# nanoPhant.net
KiCad netlist of a schematic drawn in EAGLE
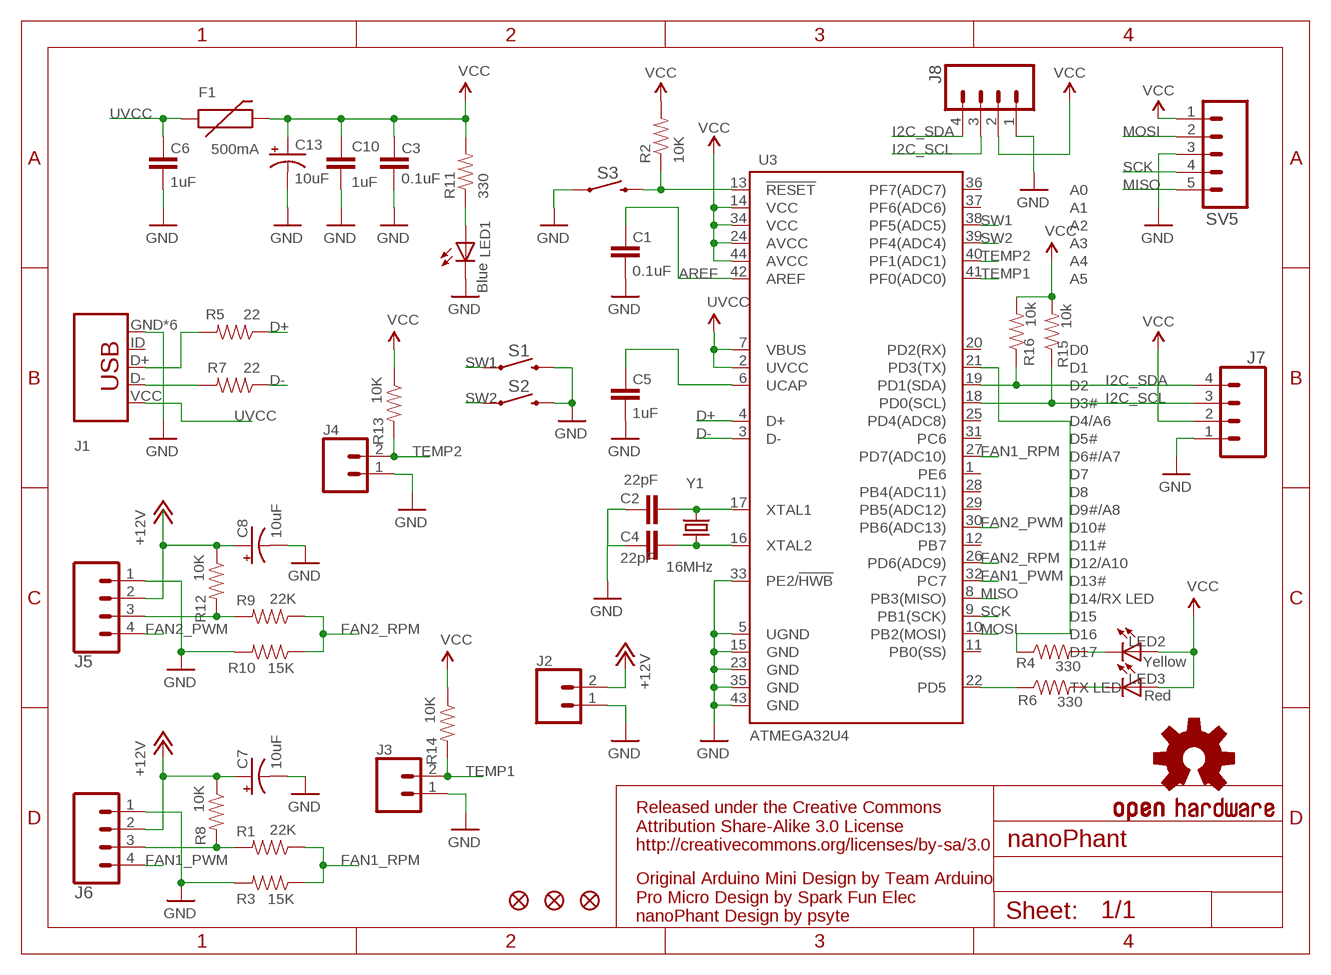
[diagram p0: schematic, sheet 1]

(export (version "E")
  (design (tool "Eeschema 10.0.6"))
  (components
    (comp (ref "C1")
      (value "0.1uF")
      (footprint "eagle-import:C0603")
      (libsource (lib "eagle-import") (part "C-EUC0603"))
    )
    (comp (ref "C2")
      (value "22pF")
      (footprint "eagle-import:C0603")
      (libsource (lib "eagle-import") (part "C-EUC0603"))
    )
    (comp (ref "C3")
      (value "0.1uF")
      (footprint "eagle-import:C0603")
      (libsource (lib "eagle-import") (part "C-EUC0603"))
    )
    (comp (ref "C4")
      (value "22pF")
      (footprint "eagle-import:C0603")
      (libsource (lib "eagle-import") (part "C-EUC0603"))
    )
    (comp (ref "C5")
      (value "1uF")
      (footprint "eagle-import:C0603")
      (libsource (lib "eagle-import") (part "C-EUC0603"))
    )
    (comp (ref "C6")
      (value "1uF")
      (footprint "eagle-import:C0603")
      (libsource (lib "eagle-import") (part "C-EUC0603"))
    )
    (comp (ref "C7")
      (value "10uF")
      (footprint "eagle-import:EIA3216")
      (libsource (lib "eagle-import") (part "CAP_POL1206"))
    )
    (comp (ref "C8")
      (value "10uF")
      (footprint "eagle-import:EIA3216")
      (libsource (lib "eagle-import") (part "CAP_POL1206"))
    )
    (comp (ref "C10")
      (value "1uF")
      (footprint "eagle-import:C0603")
      (libsource (lib "eagle-import") (part "C-EUC0603"))
    )
    (comp (ref "C13")
      (value "10uF")
      (footprint "eagle-import:EIA3216")
      (libsource (lib "eagle-import") (part "CAP_POL1206"))
    )
    (comp (ref "F1")
      (value "500mA")
      (footprint "eagle-import:PTC-1206")
      (libsource (lib "eagle-import") (part "PTCSMD"))
    )
    (comp (ref "FD1")
      (value "FIDUCIAL1X2")
      (footprint "eagle-import:FIDUCIAL-1X2")
      (libsource (lib "eagle-import") (part "FIDUCIAL1X2"))
    )
    (comp (ref "FD2")
      (value "FIDUCIAL1X2")
      (footprint "eagle-import:FIDUCIAL-1X2")
      (libsource (lib "eagle-import") (part "FIDUCIAL1X2"))
    )
    (comp (ref "FD3")
      (value "FIDUCIAL1X2")
      (footprint "eagle-import:FIDUCIAL-1X2")
      (libsource (lib "eagle-import") (part "FIDUCIAL1X2"))
    )
    (comp (ref "J1")
      (value "AMP FCI 10103594-0001LF")
      (footprint "eagle-import:MICRO_USB_4_LEGS")
      (libsource (lib "eagle-import") (part "MICRO-USB-B"))
    )
    (comp (ref "J2")
      (value "CONN_02")
      (footprint "eagle-import:1X02")
      (libsource (lib "eagle-import") (part "CONN_02"))
    )
    (comp (ref "J3")
      (value "CONN_02")
      (footprint "eagle-import:1X02")
      (libsource (lib "eagle-import") (part "CONN_02"))
    )
    (comp (ref "J4")
      (value "CONN_02")
      (footprint "eagle-import:1X02")
      (libsource (lib "eagle-import") (part "CONN_02"))
    )
    (comp (ref "J5")
      (value "CONN_04")
      (footprint "eagle-import:1X04")
      (libsource (lib "eagle-import") (part "CONN_04"))
    )
    (comp (ref "J6")
      (value "CONN_04")
      (footprint "eagle-import:1X04")
      (libsource (lib "eagle-import") (part "CONN_04"))
    )
    (comp (ref "J7")
      (value "CONN_04")
      (footprint "eagle-import:1X04")
      (libsource (lib "eagle-import") (part "CONN_04"))
    )
    (comp (ref "J8")
      (value "CONN_04")
      (footprint "eagle-import:1X04")
      (libsource (lib "eagle-import") (part "CONN_04"))
    )
    (comp (ref "LED1")
      (value "Blue")
      (footprint "eagle-import:LED-0603")
      (libsource (lib "eagle-import") (part "LED0603"))
    )
    (comp (ref "LED2")
      (value "Yellow")
      (footprint "eagle-import:LED-0603")
      (libsource (lib "eagle-import") (part "LED0603"))
    )
    (comp (ref "LED3")
      (value "Red")
      (footprint "eagle-import:LED-0603")
      (libsource (lib "eagle-import") (part "LED0603"))
    )
    (comp (ref "R1")
      (value "22K")
      (footprint "eagle-import:0603-RES")
      (libsource (lib "eagle-import") (part "RESISTOR0603-RES"))
    )
    (comp (ref "R2")
      (value "10K")
      (footprint "eagle-import:0603-RES")
      (libsource (lib "eagle-import") (part "RESISTOR0603-RES"))
    )
    (comp (ref "R3")
      (value "15K")
      (footprint "eagle-import:0603-RES")
      (libsource (lib "eagle-import") (part "RESISTOR0603-RES"))
    )
    (comp (ref "R4")
      (value "330")
      (footprint "eagle-import:0603-RES")
      (libsource (lib "eagle-import") (part "RESISTOR0603-RES"))
    )
    (comp (ref "R5")
      (value "22")
      (footprint "eagle-import:0603-RES")
      (libsource (lib "eagle-import") (part "RESISTOR0603-RES"))
    )
    (comp (ref "R6")
      (value "330")
      (footprint "eagle-import:0603-RES")
      (libsource (lib "eagle-import") (part "RESISTOR0603-RES"))
    )
    (comp (ref "R7")
      (value "22")
      (footprint "eagle-import:0603-RES")
      (libsource (lib "eagle-import") (part "RESISTOR0603-RES"))
    )
    (comp (ref "R8")
      (value "10K")
      (footprint "eagle-import:0603-RES")
      (libsource (lib "eagle-import") (part "RESISTOR0603-RES"))
    )
    (comp (ref "R9")
      (value "22K")
      (footprint "eagle-import:0603-RES")
      (libsource (lib "eagle-import") (part "RESISTOR0603-RES"))
    )
    (comp (ref "R10")
      (value "15K")
      (footprint "eagle-import:0603-RES")
      (libsource (lib "eagle-import") (part "RESISTOR0603-RES"))
    )
    (comp (ref "R11")
      (value "330")
      (footprint "eagle-import:0603-RES")
      (libsource (lib "eagle-import") (part "RESISTOR0603-RES"))
    )
    (comp (ref "R12")
      (value "10K")
      (footprint "eagle-import:0603-RES")
      (libsource (lib "eagle-import") (part "RESISTOR0603-RES"))
    )
    (comp (ref "R13")
      (value "10K")
      (footprint "eagle-import:0603-RES")
      (libsource (lib "eagle-import") (part "RESISTOR0603-RES"))
    )
    (comp (ref "R14")
      (value "10K")
      (footprint "eagle-import:0603-RES")
      (libsource (lib "eagle-import") (part "RESISTOR0603-RES"))
    )
    (comp (ref "R15")
      (value "10k")
      (footprint "eagle-import:0603-RES")
      (libsource (lib "eagle-import") (part "RESISTOR0603-RES"))
    )
    (comp (ref "R16")
      (value "10k")
      (footprint "eagle-import:0603-RES")
      (libsource (lib "eagle-import") (part "RESISTOR0603-RES"))
    )
    (comp (ref "S1")
      (value "MOMENTARY-SWITCH-SPST-SMD-6.0X3.5MM")
      (footprint "eagle-import:TACTILE_SWITCH_SMD_6.0X3.5MM")
      (libsource (lib "eagle-import") (part "MOMENTARY-SWITCH-SPST-SMD-6.0X3.5MM"))
    )
    (comp (ref "S2")
      (value "MOMENTARY-SWITCH-SPST-SMD-6.0X3.5MM")
      (footprint "eagle-import:TACTILE_SWITCH_SMD_6.0X3.5MM")
      (libsource (lib "eagle-import") (part "MOMENTARY-SWITCH-SPST-SMD-6.0X3.5MM"))
    )
    (comp (ref "S3")
      (value "MOMENTARY-SWITCH-SPST-SMD-6.0X3.5MM")
      (footprint "eagle-import:TACTILE_SWITCH_SMD_6.0X3.5MM")
      (libsource (lib "eagle-import") (part "MOMENTARY-SWITCH-SPST-SMD-6.0X3.5MM"))
    )
    (comp (ref "SV5")
      (value "CONN_05")
      (footprint "eagle-import:1X05")
      (libsource (lib "eagle-import") (part "CONN_05"))
    )
    (comp (ref "U$3")
      (value "OSHW-LOGOS")
      (footprint "eagle-import:OSHW-LOGO-S")
      (libsource (lib "eagle-import") (part "OSHW-LOGOS"))
    )
    (comp (ref "U3")
      (value "ATMEGA32U4")
      (footprint "eagle-import:QFN-44-NOPAD_1_1-OUTFAKES")
      (libsource (lib "eagle-import") (part "ATMEGA32U4OUTFAKES"))
    )
    (comp (ref "Y1")
      (value "16MHz")
      (footprint "eagle-import:CRYSTAL-SMD-5X3")
      (libsource (lib "eagle-import") (part "CRYSTAL5X3"))
    )
  )
  (nets
    (net (code "1") (name "+12V") (class "Default")
      (node (ref "C7") (pin "A") (pinfunction "+_A") (pintype "passive"))
      (node (ref "C8") (pin "A") (pinfunction "+_A") (pintype "passive"))
      (node (ref "J2") (pin "2") (pinfunction "2_2") (pintype "passive"))
      (node (ref "J5") (pin "2") (pinfunction "2_2") (pintype "passive"))
      (node (ref "J6") (pin "2") (pinfunction "2_2") (pintype "passive"))
      (node (ref "R12") (pin "1") (pinfunction "1_1") (pintype "passive"))
      (node (ref "R8") (pin "1") (pinfunction "1_1") (pintype "passive"))
    )
    (net (code "2") (name "/AREF") (class "Default")
      (node (ref "C1") (pin "2") (pinfunction "2_2") (pintype "passive"))
      (node (ref "U3") (pin "42") (pinfunction "AREF_42") (pintype "bidirectional"))
    )
    (net (code "3") (name "/D+") (class "Default")
      (node (ref "R5") (pin "1") (pinfunction "1_1") (pintype "passive"))
      (node (ref "U3") (pin "4") (pinfunction "D+_4") (pintype "bidirectional"))
    )
    (net (code "4") (name "/D-") (class "Default")
      (node (ref "R7") (pin "1") (pinfunction "1_1") (pintype "passive"))
      (node (ref "U3") (pin "3") (pinfunction "D-_3") (pintype "bidirectional"))
    )
    (net (code "5") (name "/FAN1_PWM") (class "Default")
      (node (ref "J6") (pin "4") (pinfunction "4_4") (pintype "passive"))
      (node (ref "U3") (pin "32") (pinfunction "PC7_32") (pintype "bidirectional"))
    )
    (net (code "6") (name "/FAN1_RPM") (class "Default")
      (node (ref "R1") (pin "1") (pinfunction "1_1") (pintype "passive"))
      (node (ref "R3") (pin "1") (pinfunction "1_1") (pintype "passive"))
      (node (ref "U3") (pin "27") (pinfunction "PD7(ADC10)_27") (pintype "bidirectional"))
    )
    (net (code "7") (name "/FAN2_PWM") (class "Default")
      (node (ref "J5") (pin "4") (pinfunction "4_4") (pintype "passive"))
      (node (ref "U3") (pin "30") (pinfunction "PB6(ADC13)_30") (pintype "bidirectional"))
    )
    (net (code "8") (name "/FAN2_RPM") (class "Default")
      (node (ref "R10") (pin "1") (pinfunction "1_1") (pintype "passive"))
      (node (ref "R9") (pin "1") (pinfunction "1_1") (pintype "passive"))
      (node (ref "U3") (pin "26") (pinfunction "PD6(ADC9)_26") (pintype "bidirectional"))
    )
    (net (code "9") (name "/I2C_SCL") (class "Default")
      (node (ref "J7") (pin "3") (pinfunction "3_3") (pintype "passive"))
      (node (ref "J8") (pin "3") (pinfunction "3_3") (pintype "passive"))
      (node (ref "R15") (pin "1") (pinfunction "1_1") (pintype "passive"))
      (node (ref "U3") (pin "18") (pinfunction "PD0(SCL)_18") (pintype "bidirectional"))
    )
    (net (code "10") (name "/I2C_SDA") (class "Default")
      (node (ref "J7") (pin "4") (pinfunction "4_4") (pintype "passive"))
      (node (ref "J8") (pin "4") (pinfunction "4_4") (pintype "passive"))
      (node (ref "R16") (pin "1") (pinfunction "1_1") (pintype "passive"))
      (node (ref "U3") (pin "19") (pinfunction "PD1(SDA)_19") (pintype "bidirectional"))
    )
    (net (code "11") (name "/MISO") (class "Default")
      (node (ref "SV5") (pin "5") (pinfunction "5_5") (pintype "passive"))
      (node (ref "U3") (pin "8") (pinfunction "PB3(MISO)_8") (pintype "bidirectional"))
    )
    (net (code "12") (name "/MOSI") (class "Default")
      (node (ref "SV5") (pin "2") (pinfunction "2_2") (pintype "passive"))
      (node (ref "U3") (pin "10") (pinfunction "PB2(MOSI)_10") (pintype "bidirectional"))
    )
    (net (code "13") (name "/SCK") (class "Default")
      (node (ref "SV5") (pin "4") (pinfunction "4_4") (pintype "passive"))
      (node (ref "U3") (pin "9") (pinfunction "PB1(SCK)_9") (pintype "bidirectional"))
    )
    (net (code "14") (name "/SW1") (class "Default")
      (node (ref "S1") (pin "1") (pinfunction "1_1") (pintype "passive"))
      (node (ref "U3") (pin "38") (pinfunction "PF5(ADC5)_38") (pintype "bidirectional"))
    )
    (net (code "15") (name "/SW2") (class "Default")
      (node (ref "S2") (pin "1") (pinfunction "1_1") (pintype "passive"))
      (node (ref "U3") (pin "39") (pinfunction "PF4(ADC4)_39") (pintype "bidirectional"))
    )
    (net (code "16") (name "/TEMP1") (class "Default")
      (node (ref "J3") (pin "2") (pinfunction "2_2") (pintype "passive"))
      (node (ref "R14") (pin "2") (pinfunction "2_2") (pintype "passive"))
      (node (ref "U3") (pin "41") (pinfunction "PF0(ADC0)_41") (pintype "bidirectional"))
    )
    (net (code "17") (name "/TEMP2") (class "Default")
      (node (ref "J4") (pin "2") (pinfunction "2_2") (pintype "passive"))
      (node (ref "R13") (pin "2") (pinfunction "2_2") (pintype "passive"))
      (node (ref "U3") (pin "40") (pinfunction "PF1(ADC1)_40") (pintype "bidirectional"))
    )
    (net (code "18") (name "GND") (class "Default")
      (node (ref "C1") (pin "1") (pinfunction "1_1") (pintype "passive"))
      (node (ref "C10") (pin "2") (pinfunction "2_2") (pintype "passive"))
      (node (ref "C13") (pin "C") (pinfunction "-_C") (pintype "passive"))
      (node (ref "C2") (pin "2") (pinfunction "2_2") (pintype "passive"))
      (node (ref "C3") (pin "1") (pinfunction "1_1") (pintype "passive"))
      (node (ref "C4") (pin "2") (pinfunction "2_2") (pintype "passive"))
      (node (ref "C5") (pin "1") (pinfunction "1_1") (pintype "passive"))
      (node (ref "C6") (pin "1") (pinfunction "1_1") (pintype "passive"))
      (node (ref "C7") (pin "C") (pinfunction "-_C") (pintype "passive"))
      (node (ref "C8") (pin "C") (pinfunction "-_C") (pintype "passive"))
      (node (ref "J1") (pin "GND") (pinfunction "GND_GND") (pintype "bidirectional"))
      (node (ref "J1") (pin "P$1") (pinfunction "GND_P$1") (pintype "bidirectional"))
      (node (ref "J1") (pin "P$2") (pinfunction "GND_P$2") (pintype "bidirectional"))
      (node (ref "J1") (pin "P$3") (pinfunction "GND_P$3") (pintype "bidirectional"))
      (node (ref "J1") (pin "P$4") (pinfunction "GND_P$4") (pintype "bidirectional"))
      (node (ref "J1") (pin "P$5") (pinfunction "GND_P$5") (pintype "bidirectional"))
      (node (ref "J2") (pin "1") (pinfunction "1_1") (pintype "passive"))
      (node (ref "J3") (pin "1") (pinfunction "1_1") (pintype "passive"))
      (node (ref "J4") (pin "1") (pinfunction "1_1") (pintype "passive"))
      (node (ref "J5") (pin "1") (pinfunction "1_1") (pintype "passive"))
      (node (ref "J6") (pin "1") (pinfunction "1_1") (pintype "passive"))
      (node (ref "J7") (pin "1") (pinfunction "1_1") (pintype "passive"))
      (node (ref "J8") (pin "1") (pinfunction "1_1") (pintype "passive"))
      (node (ref "LED1") (pin "C") (pinfunction "C_C") (pintype "passive"))
      (node (ref "R10") (pin "2") (pinfunction "2_2") (pintype "passive"))
      (node (ref "R3") (pin "2") (pinfunction "2_2") (pintype "passive"))
      (node (ref "S1") (pin "2") (pinfunction "2_2") (pintype "passive"))
      (node (ref "S2") (pin "2") (pinfunction "2_2") (pintype "passive"))
      (node (ref "S3") (pin "1") (pinfunction "1_1") (pintype "passive"))
      (node (ref "SV5") (pin "3") (pinfunction "3_3") (pintype "passive"))
      (node (ref "U3") (pin "15") (pinfunction "GND_15") (pintype "bidirectional"))
      (node (ref "U3") (pin "23") (pinfunction "GND_23") (pintype "bidirectional"))
      (node (ref "U3") (pin "33") (pinfunction "PE2/~{HWB}_33") (pintype "bidirectional"))
      (node (ref "U3") (pin "35") (pinfunction "GND_35") (pintype "bidirectional"))
      (node (ref "U3") (pin "43") (pinfunction "GND_43") (pintype "bidirectional"))
      (node (ref "U3") (pin "5") (pinfunction "UGND_5") (pintype "bidirectional"))
    )
    (net (code "19") (name "Net-(J1-PadD+)") (class "Default")
      (node (ref "J1") (pin "D+") (pinfunction "D+_D+") (pintype "bidirectional"))
      (node (ref "R5") (pin "2") (pinfunction "2_2") (pintype "passive"))
    )
    (net (code "20") (name "Net-(J1-PadD-)") (class "Default")
      (node (ref "J1") (pin "D-") (pinfunction "D-_D-") (pintype "bidirectional"))
      (node (ref "R7") (pin "2") (pinfunction "2_2") (pintype "passive"))
    )
    (net (code "21") (name "Net-(J5-Pad3)") (class "Default")
      (node (ref "J5") (pin "3") (pinfunction "3_3") (pintype "passive"))
      (node (ref "R12") (pin "2") (pinfunction "2_2") (pintype "passive"))
      (node (ref "R9") (pin "2") (pinfunction "2_2") (pintype "passive"))
    )
    (net (code "22") (name "Net-(J6-Pad3)") (class "Default")
      (node (ref "J6") (pin "3") (pinfunction "3_3") (pintype "passive"))
      (node (ref "R1") (pin "2") (pinfunction "2_2") (pintype "passive"))
      (node (ref "R8") (pin "2") (pinfunction "2_2") (pintype "passive"))
    )
    (net (code "23") (name "Net-(LED1-PadA)") (class "Default")
      (node (ref "LED1") (pin "A") (pinfunction "A_A") (pintype "passive"))
      (node (ref "R11") (pin "1") (pinfunction "1_1") (pintype "passive"))
    )
    (net (code "24") (name "Net-(LED2-PadC)") (class "Default")
      (node (ref "LED2") (pin "C") (pinfunction "C_C") (pintype "passive"))
      (node (ref "R4") (pin "2") (pinfunction "2_2") (pintype "passive"))
    )
    (net (code "25") (name "Net-(LED3-PadC)") (class "Default")
      (node (ref "LED3") (pin "C") (pinfunction "C_C") (pintype "passive"))
      (node (ref "R6") (pin "2") (pinfunction "2_2") (pintype "passive"))
    )
    (net (code "26") (name "Net-(U3-PD3(TX))") (class "Default")
      (node (ref "R4") (pin "1") (pinfunction "1_1") (pintype "passive"))
      (node (ref "U3") (pin "21") (pinfunction "PD3(TX)_21") (pintype "bidirectional"))
    )
    (net (code "27") (name "Net-(U3-PD5)") (class "Default")
      (node (ref "R6") (pin "1") (pinfunction "1_1") (pintype "passive"))
      (node (ref "U3") (pin "22") (pinfunction "PD5_22") (pintype "bidirectional"))
    )
    (net (code "28") (name "Net-(U3-UCAP)") (class "Default")
      (node (ref "C5") (pin "2") (pinfunction "2_2") (pintype "passive"))
      (node (ref "U3") (pin "6") (pinfunction "UCAP_6") (pintype "bidirectional"))
    )
    (net (code "29") (name "Net-(U3-XTAL1)") (class "Default")
      (node (ref "C2") (pin "1") (pinfunction "1_1") (pintype "passive"))
      (node (ref "U3") (pin "17") (pinfunction "XTAL1_17") (pintype "bidirectional"))
      (node (ref "Y1") (pin "3") (pinfunction "2_3") (pintype "passive"))
    )
    (net (code "30") (name "Net-(U3-XTAL2)") (class "Default")
      (node (ref "C4") (pin "1") (pinfunction "1_1") (pintype "passive"))
      (node (ref "U3") (pin "16") (pinfunction "XTAL2_16") (pintype "bidirectional"))
      (node (ref "Y1") (pin "1") (pinfunction "1_1") (pintype "passive"))
    )
    (net (code "31") (name "Net-(U3-~{RESET})") (class "Default")
      (node (ref "R2") (pin "1") (pinfunction "1_1") (pintype "passive"))
      (node (ref "S3") (pin "2") (pinfunction "2_2") (pintype "passive"))
      (node (ref "U3") (pin "13") (pinfunction "~{RESET}_13") (pintype "bidirectional"))
    )
    (net (code "32") (name "UVCC") (class "Default")
      (node (ref "C6") (pin "2") (pinfunction "2_2") (pintype "passive"))
      (node (ref "F1") (pin "1") (pinfunction "1_1") (pintype "bidirectional"))
      (node (ref "J1") (pin "VCC") (pinfunction "VBUS_VCC") (pintype "bidirectional"))
      (node (ref "U3") (pin "2") (pinfunction "UVCC_2") (pintype "bidirectional"))
      (node (ref "U3") (pin "7") (pinfunction "VBUS_7") (pintype "bidirectional"))
    )
    (net (code "33") (name "VCC") (class "Default")
      (node (ref "C10") (pin "1") (pinfunction "1_1") (pintype "passive"))
      (node (ref "C13") (pin "A") (pinfunction "+_A") (pintype "passive"))
      (node (ref "C3") (pin "2") (pinfunction "2_2") (pintype "passive"))
      (node (ref "F1") (pin "2") (pinfunction "2_2") (pintype "bidirectional"))
      (node (ref "J7") (pin "2") (pinfunction "2_2") (pintype "passive"))
      (node (ref "J8") (pin "2") (pinfunction "2_2") (pintype "passive"))
      (node (ref "LED2") (pin "A") (pinfunction "A_A") (pintype "passive"))
      (node (ref "LED3") (pin "A") (pinfunction "A_A") (pintype "passive"))
      (node (ref "R11") (pin "2") (pinfunction "2_2") (pintype "passive"))
      (node (ref "R13") (pin "1") (pinfunction "1_1") (pintype "passive"))
      (node (ref "R14") (pin "1") (pinfunction "1_1") (pintype "passive"))
      (node (ref "R15") (pin "2") (pinfunction "2_2") (pintype "passive"))
      (node (ref "R16") (pin "2") (pinfunction "2_2") (pintype "passive"))
      (node (ref "R2") (pin "2") (pinfunction "2_2") (pintype "passive"))
      (node (ref "SV5") (pin "1") (pinfunction "1_1") (pintype "passive"))
      (node (ref "U3") (pin "14") (pinfunction "VCC_14") (pintype "bidirectional"))
      (node (ref "U3") (pin "24") (pinfunction "AVCC_24") (pintype "bidirectional"))
      (node (ref "U3") (pin "34") (pinfunction "VCC_34") (pintype "bidirectional"))
      (node (ref "U3") (pin "44") (pinfunction "AVCC_44") (pintype "bidirectional"))
    )
    (net (code "34") (name "unconnected-(J1-PadID)") (class "Default")
      (node (ref "J1") (pin "ID") (pinfunction "ID_ID") (pintype "bidirectional"))
    )
    (net (code "35") (name "unconnected-(U3-PB0(SS)-Pad11)") (class "Default")
      (node (ref "U3") (pin "11") (pinfunction "PB0(SS)_11") (pintype "bidirectional"))
    )
    (net (code "36") (name "unconnected-(U3-PB4(ADC11)-Pad28)") (class "Default")
      (node (ref "U3") (pin "28") (pinfunction "PB4(ADC11)_28") (pintype "bidirectional"))
    )
    (net (code "37") (name "unconnected-(U3-PB5(ADC12)-Pad29)") (class "Default")
      (node (ref "U3") (pin "29") (pinfunction "PB5(ADC12)_29") (pintype "bidirectional"))
    )
    (net (code "38") (name "unconnected-(U3-PB7-Pad12)") (class "Default")
      (node (ref "U3") (pin "12") (pinfunction "PB7_12") (pintype "bidirectional"))
    )
    (net (code "39") (name "unconnected-(U3-PC6-Pad31)") (class "Default")
      (node (ref "U3") (pin "31") (pinfunction "PC6_31") (pintype "bidirectional"))
    )
    (net (code "40") (name "unconnected-(U3-PD2(RX)-Pad20)") (class "Default")
      (node (ref "U3") (pin "20") (pinfunction "PD2(RX)_20") (pintype "bidirectional"))
    )
    (net (code "41") (name "unconnected-(U3-PD4(ADC8)-Pad25)") (class "Default")
      (node (ref "U3") (pin "25") (pinfunction "PD4(ADC8)_25") (pintype "bidirectional"))
    )
    (net (code "42") (name "unconnected-(U3-PE6-Pad1)") (class "Default")
      (node (ref "U3") (pin "1") (pinfunction "PE6_1") (pintype "bidirectional"))
    )
    (net (code "43") (name "unconnected-(U3-PF6(ADC6)-Pad37)") (class "Default")
      (node (ref "U3") (pin "37") (pinfunction "PF6(ADC6)_37") (pintype "bidirectional"))
    )
    (net (code "44") (name "unconnected-(U3-PF7(ADC7)-Pad36)") (class "Default")
      (node (ref "U3") (pin "36") (pinfunction "PF7(ADC7)_36") (pintype "bidirectional"))
    )
  )
)
